# ESP8266.net
KiCad netlist of a schematic drawn in Altium Designer
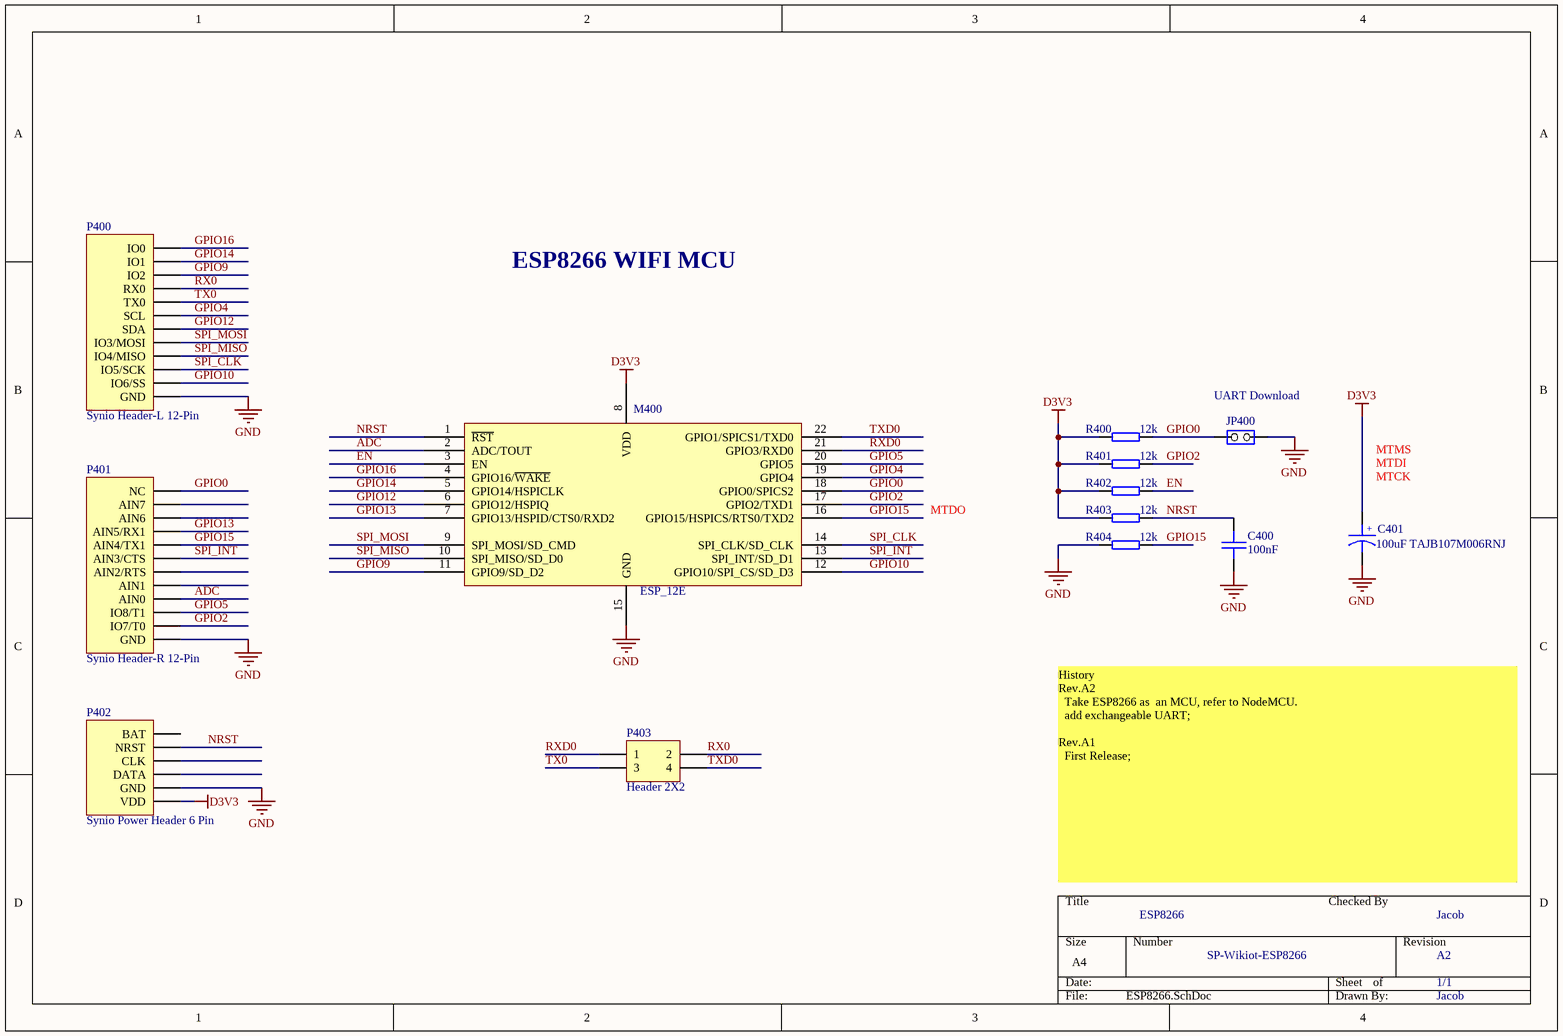
[diagram p0: ESP8266.SchDoc]

(export (version "E")
  (design (tool "Eeschema 10.0.6"))
  (components
    (comp (ref "C400")
      (value "100nF")
      (footprint "C0603L")
      (description "Surface mount capacitor 0402")
      (libsource (lib "Vowstar_Basic_Device") (part "SMT_C_0402"))
    )
    (comp (ref "C401")
      (value "100uF TAJB107M006RNJ")
      (footprint "SMT_C_Tantalum_B")
      (description "Capacitor, SM Tantalum; Body 3.5 x 2.8 mm (LxW typ)")
      (libsource (lib "Vowstar_Basic_Device") (part "SMT_C_Tantalum_B"))
    )
    (comp (ref "JP400")
      (value "UART Download")
      (footprint "SIP2")
      (description "Jumper2")
      (libsource (lib "Misc") (part "Jumper2-2"))
    )
    (comp (ref "M400")
      (value "ESP_12E")
      (footprint "ESP_12E")
      (description "ESP-12 Wi-Fi Module by AI-Thinker")
      (libsource (lib "Misc") (part "ESP_12E"))
    )
    (comp (ref "P400")
      (value "Synio Header-L 12-Pin")
      (footprint "HDR1X12/2.54MM")
      (description "Synio Header-L, 12-Pin")
      (fields (field (name "PUBLISHER") "Altium Limited"))
      (libsource (lib "Connector") (part "Synio Header-L 12-Pin"))
    )
    (comp (ref "P401")
      (value "Synio Header-R 12-Pin")
      (footprint "HDR1X12/2.54MM")
      (description "Synio Header-R, 12-Pin")
      (fields (field (name "PUBLISHER") "Altium Limited"))
      (libsource (lib "Connector") (part "Synio Header-R 12-Pin"))
    )
    (comp (ref "P402")
      (value "Synio Power Header 6 Pin")
      (footprint "HDR1X6/2.54MM")
      (libsource (lib "Connector") (part "Synio Power Header 6 Pin"))
    )
    (comp (ref "P403")
      (value "Header 2X2")
      (footprint "JUMPER4_SMD")
      (description "Header, 2-Pin, Dual row")
      (fields (field (name "PUBLISHER") "Altium Limited"))
      (libsource (lib "Miscellaneous Connectors") (part "Header 2X2"))
    )
    (comp (ref "R400")
      (value "12k")
      (footprint "R0603")
      (description "Surface mount resistor 0402")
      (libsource (lib "Vowstar_Basic_Device") (part "SMT_R_0402"))
    )
    (comp (ref "R401")
      (value "12k")
      (footprint "R0603")
      (description "Surface mount resistor 0402")
      (libsource (lib "Vowstar_Basic_Device") (part "SMT_R_0402"))
    )
    (comp (ref "R402")
      (value "12k")
      (footprint "R0603")
      (description "Surface mount resistor 0402")
      (libsource (lib "Vowstar_Basic_Device") (part "SMT_R_0402"))
    )
    (comp (ref "R403")
      (value "12k")
      (footprint "R0603")
      (description "Surface mount resistor 0402")
      (libsource (lib "Vowstar_Basic_Device") (part "SMT_R_0402"))
    )
    (comp (ref "R404")
      (value "12k")
      (footprint "R0603")
      (description "Surface mount resistor 0402")
      (libsource (lib "Vowstar_Basic_Device") (part "SMT_R_0402"))
    )
  )
  (nets
    (net (code "1") (name "/ADC") (class "Default")
      (node (ref "M400") (pin "2") (pinfunction "ADC/TOUT_2") (pintype "passive"))
      (node (ref "P401") (pin "4") (pinfunction "AIN0_4") (pintype "passive"))
    )
    (net (code "2") (name "/EN") (class "Default")
      (node (ref "M400") (pin "3") (pinfunction "EN_3") (pintype "passive"))
      (node (ref "R402") (pin "2") (pinfunction "2_2") (pintype "passive"))
    )
    (net (code "3") (name "/GPIO0") (class "Default")
      (node (ref "JP400") (pin "2") (pinfunction "NO_2") (pintype "passive"))
      (node (ref "M400") (pin "18") (pinfunction "GPIO0/SPICS2_18") (pintype "passive"))
      (node (ref "P401") (pin "12") (pinfunction "NC_12") (pintype "passive"))
      (node (ref "R400") (pin "2") (pinfunction "2_2") (pintype "passive"))
    )
    (net (code "4") (name "/GPIO2") (class "Default")
      (node (ref "M400") (pin "17") (pinfunction "GPIO2/TXD1_17") (pintype "passive"))
      (node (ref "P401") (pin "2") (pinfunction "IO7/T0_2") (pintype "passive"))
      (node (ref "R401") (pin "2") (pinfunction "2_2") (pintype "passive"))
    )
    (net (code "5") (name "/GPIO4") (class "Default")
      (node (ref "M400") (pin "19") (pinfunction "GPIO4_19") (pintype "passive"))
      (node (ref "P400") (pin "7") (pinfunction "SCL_7") (pintype "passive"))
    )
    (net (code "6") (name "/GPIO5") (class "Default")
      (node (ref "M400") (pin "20") (pinfunction "GPIO5_20") (pintype "passive"))
      (node (ref "P401") (pin "3") (pinfunction "IO8/T1_3") (pintype "passive"))
    )
    (net (code "7") (name "/GPIO9") (class "Default")
      (node (ref "M400") (pin "11") (pinfunction "GPIO9/SD_D2_11") (pintype "passive"))
      (node (ref "P400") (pin "10") (pinfunction "IO2_10") (pintype "passive"))
    )
    (net (code "8") (name "/GPIO10") (class "Default")
      (node (ref "M400") (pin "12") (pinfunction "GPIO10/SPI_CS/SD_D3_12") (pintype "passive"))
      (node (ref "P400") (pin "2") (pinfunction "IO6/SS_2") (pintype "passive"))
    )
    (net (code "9") (name "/GPIO12") (class "Default")
      (node (ref "M400") (pin "6") (pinfunction "GPIO12/HSPIQ_6") (pintype "passive"))
      (node (ref "P400") (pin "6") (pinfunction "SDA_6") (pintype "passive"))
    )
    (net (code "10") (name "/GPIO13") (class "Default")
      (node (ref "M400") (pin "7") (pinfunction "GPIO13/HSPID/CTS0/RXD2_7") (pintype "passive"))
      (node (ref "P401") (pin "9") (pinfunction "AIN5/RX1_9") (pintype "passive"))
    )
    (net (code "11") (name "/GPIO14") (class "Default")
      (node (ref "M400") (pin "5") (pinfunction "GPIO14/HSPICLK_5") (pintype "passive"))
      (node (ref "P400") (pin "11") (pinfunction "IO1_11") (pintype "passive"))
    )
    (net (code "12") (name "/GPIO15") (class "Default")
      (node (ref "M400") (pin "16") (pinfunction "GPIO15/HSPICS/RTS0/TXD2_16") (pintype "passive"))
      (node (ref "P401") (pin "8") (pinfunction "AIN4/TX1_8") (pintype "passive"))
      (node (ref "R404") (pin "2") (pinfunction "2_2") (pintype "passive"))
    )
    (net (code "13") (name "/GPIO16") (class "Default")
      (node (ref "M400") (pin "4") (pinfunction "GPIO16/~{WAKE}_4") (pintype "passive"))
      (node (ref "P400") (pin "12") (pinfunction "IO0_12") (pintype "passive"))
    )
    (net (code "14") (name "/NRST") (class "Default")
      (node (ref "C400") (pin "1") (pinfunction "1_1") (pintype "passive"))
      (node (ref "M400") (pin "1") (pinfunction "~{RST}_1") (pintype "passive"))
      (node (ref "P402") (pin "5") (pinfunction "NRST_5") (pintype "passive"))
      (node (ref "R403") (pin "2") (pinfunction "2_2") (pintype "passive"))
    )
    (net (code "15") (name "/RX0") (class "Default")
      (node (ref "P400") (pin "9") (pinfunction "RX0_9") (pintype "passive"))
      (node (ref "P403") (pin "2") (pinfunction "2_2") (pintype "passive"))
    )
    (net (code "16") (name "/RXD0") (class "Default")
      (node (ref "M400") (pin "21") (pinfunction "GPIO3/RXD0_21") (pintype "passive"))
      (node (ref "P403") (pin "1") (pinfunction "1_1") (pintype "passive"))
    )
    (net (code "17") (name "/SPI_CLK") (class "Default")
      (node (ref "M400") (pin "14") (pinfunction "SPI_CLK/SD_CLK_14") (pintype "passive"))
      (node (ref "P400") (pin "3") (pinfunction "IO5/SCK_3") (pintype "passive"))
    )
    (net (code "18") (name "/SPI_INT") (class "Default")
      (node (ref "M400") (pin "13") (pinfunction "SPI_INT/SD_D1_13") (pintype "passive"))
      (node (ref "P401") (pin "7") (pinfunction "AIN3/CTS_7") (pintype "passive"))
    )
    (net (code "19") (name "/SPI_MISO") (class "Default")
      (node (ref "M400") (pin "10") (pinfunction "SPI_MISO/SD_D0_10") (pintype "passive"))
      (node (ref "P400") (pin "4") (pinfunction "IO4/MISO_4") (pintype "passive"))
    )
    (net (code "20") (name "/SPI_MOSI") (class "Default")
      (node (ref "M400") (pin "9") (pinfunction "SPI_MOSI/SD_CMD_9") (pintype "passive"))
      (node (ref "P400") (pin "5") (pinfunction "IO3/MOSI_5") (pintype "passive"))
    )
    (net (code "21") (name "/TX0") (class "Default")
      (node (ref "P400") (pin "8") (pinfunction "TX0_8") (pintype "passive"))
      (node (ref "P403") (pin "3") (pinfunction "3_3") (pintype "passive"))
    )
    (net (code "22") (name "/TXD0") (class "Default")
      (node (ref "M400") (pin "22") (pinfunction "GPIO1/SPICS1/TXD0_22") (pintype "passive"))
      (node (ref "P403") (pin "4") (pinfunction "4_4") (pintype "passive"))
    )
    (net (code "23") (name "D3V3") (class "Default")
      (node (ref "C401") (pin "1") (pinfunction "1_1") (pintype "passive"))
      (node (ref "M400") (pin "8") (pinfunction "VDD_8") (pintype "passive"))
      (node (ref "P402") (pin "1") (pinfunction "VDD_1") (pintype "passive"))
      (node (ref "R400") (pin "1") (pinfunction "1_1") (pintype "passive"))
      (node (ref "R401") (pin "1") (pinfunction "1_1") (pintype "passive"))
      (node (ref "R402") (pin "1") (pinfunction "1_1") (pintype "passive"))
      (node (ref "R403") (pin "1") (pinfunction "1_1") (pintype "passive"))
    )
    (net (code "24") (name "GND") (class "Default")
      (node (ref "C400") (pin "2") (pinfunction "2_2") (pintype "passive"))
      (node (ref "C401") (pin "2") (pinfunction "2_2") (pintype "passive"))
      (node (ref "JP400") (pin "1") (pinfunction "COMMON_1") (pintype "passive"))
      (node (ref "M400") (pin "15") (pinfunction "GND_15") (pintype "passive"))
      (node (ref "P400") (pin "1") (pinfunction "GND_1") (pintype "passive"))
      (node (ref "P401") (pin "1") (pinfunction "GND_1") (pintype "passive"))
      (node (ref "P402") (pin "2") (pinfunction "GND_2") (pintype "passive"))
      (node (ref "R404") (pin "1") (pinfunction "1_1") (pintype "passive"))
    )
    (net (code "25") (name "unconnected-(P401-AIN1-Pad5)") (class "Default")
      (node (ref "P401") (pin "5") (pinfunction "AIN1_5") (pintype "passive"))
    )
    (net (code "26") (name "unconnected-(P401-AIN2{slash}RTS-Pad6)") (class "Default")
      (node (ref "P401") (pin "6") (pinfunction "AIN2/RTS_6") (pintype "passive"))
    )
    (net (code "27") (name "unconnected-(P401-AIN6-Pad10)") (class "Default")
      (node (ref "P401") (pin "10") (pinfunction "AIN6_10") (pintype "passive"))
    )
    (net (code "28") (name "unconnected-(P401-AIN7-Pad11)") (class "Default")
      (node (ref "P401") (pin "11") (pinfunction "AIN7_11") (pintype "passive"))
    )
    (net (code "29") (name "unconnected-(P402-BAT-Pad6)") (class "Default")
      (node (ref "P402") (pin "6") (pinfunction "BAT_6") (pintype "passive"))
    )
    (net (code "30") (name "unconnected-(P402-CLK-Pad4)") (class "Default")
      (node (ref "P402") (pin "4") (pinfunction "CLK_4") (pintype "passive"))
    )
    (net (code "31") (name "unconnected-(P402-DATA-Pad3)") (class "Default")
      (node (ref "P402") (pin "3") (pinfunction "DATA_3") (pintype "passive"))
    )
  )
)
